# ESP32-WROVER_Dev_Board.net
KiCad netlist of a schematic drawn in Altium Designer
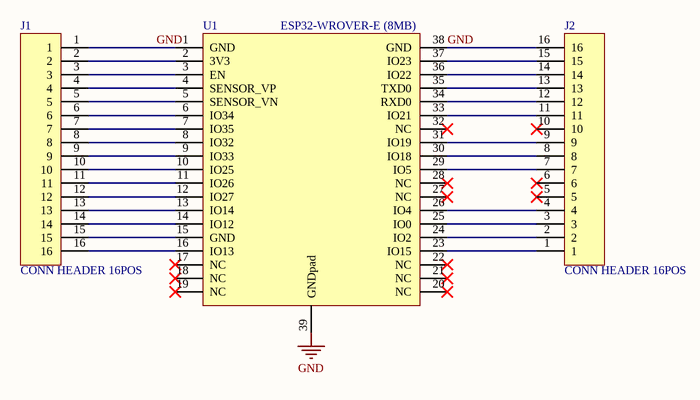
[diagram p0: ESP32-WROVER Dev Board.SchDoc]

(export (version "E")
  (design (tool "Eeschema 10.0.6"))
  (components
    (comp (ref "J1")
      (value "CONN HEADER 16POS")
      (footprint "CONN HEADER 16POS")
      (libsource (lib "") (part "CONN HEADER 16POS_1"))
    )
    (comp (ref "J2")
      (value "CONN HEADER 16POS")
      (footprint "CONN HEADER 16POS")
      (libsource (lib "G02_WSN") (part "CONN HEADER 16POS"))
    )
    (comp (ref "U1")
      (value "ESP32-WROVER-E (8MB)")
      (footprint "ESP32-WROVER-E (8MB)")
      (libsource (lib "G02_WSN") (part "ESP32-WROVER-E (8MB)"))
    )
  )
  (nets
    (net (code "1") (name "GND") (class "Default")
      (node (ref "J1") (pin "1") (pinfunction "1_1") (pintype "passive"))
      (node (ref "J2") (pin "16") (pinfunction "16_16") (pintype "passive"))
      (node (ref "U1") (pin "1") (pinfunction "GND_1") (pintype "passive"))
      (node (ref "U1") (pin "38") (pinfunction "GND_38") (pintype "passive"))
      (node (ref "U1") (pin "39") (pinfunction "GNDpad_39") (pintype "passive"))
    )
    (net (code "2") (name "Net-(J1-Pad15)") (class "Default")
      (node (ref "J1") (pin "15") (pinfunction "15_15") (pintype "passive"))
      (node (ref "U1") (pin "15") (pinfunction "GND_15") (pintype "passive"))
    )
    (net (code "3") (name "Net-(U1-3V3)") (class "Default")
      (node (ref "J1") (pin "2") (pinfunction "2_2") (pintype "passive"))
      (node (ref "U1") (pin "2") (pinfunction "3V3_2") (pintype "passive"))
    )
    (net (code "4") (name "Net-(U1-EN)") (class "Default")
      (node (ref "J1") (pin "3") (pinfunction "3_3") (pintype "passive"))
      (node (ref "U1") (pin "3") (pinfunction "EN_3") (pintype "passive"))
    )
    (net (code "5") (name "Net-(U1-IO0)") (class "Default")
      (node (ref "J2") (pin "3") (pinfunction "3_3") (pintype "passive"))
      (node (ref "U1") (pin "25") (pinfunction "IO0_25") (pintype "passive"))
    )
    (net (code "6") (name "Net-(U1-IO2)") (class "Default")
      (node (ref "J2") (pin "2") (pinfunction "2_2") (pintype "passive"))
      (node (ref "U1") (pin "24") (pinfunction "IO2_24") (pintype "passive"))
    )
    (net (code "7") (name "Net-(U1-IO4)") (class "Default")
      (node (ref "J2") (pin "4") (pinfunction "4_4") (pintype "passive"))
      (node (ref "U1") (pin "26") (pinfunction "IO4_26") (pintype "passive"))
    )
    (net (code "8") (name "Net-(U1-IO5)") (class "Default")
      (node (ref "J2") (pin "7") (pinfunction "7_7") (pintype "passive"))
      (node (ref "U1") (pin "29") (pinfunction "IO5_29") (pintype "passive"))
    )
    (net (code "9") (name "Net-(U1-IO12)") (class "Default")
      (node (ref "J1") (pin "14") (pinfunction "14_14") (pintype "passive"))
      (node (ref "U1") (pin "14") (pinfunction "IO12_14") (pintype "passive"))
    )
    (net (code "10") (name "Net-(U1-IO13)") (class "Default")
      (node (ref "J1") (pin "16") (pinfunction "16_16") (pintype "passive"))
      (node (ref "U1") (pin "16") (pinfunction "IO13_16") (pintype "passive"))
    )
    (net (code "11") (name "Net-(U1-IO14)") (class "Default")
      (node (ref "J1") (pin "13") (pinfunction "13_13") (pintype "passive"))
      (node (ref "U1") (pin "13") (pinfunction "IO14_13") (pintype "passive"))
    )
    (net (code "12") (name "Net-(U1-IO15)") (class "Default")
      (node (ref "J2") (pin "1") (pinfunction "1_1") (pintype "passive"))
      (node (ref "U1") (pin "23") (pinfunction "IO15_23") (pintype "passive"))
    )
    (net (code "13") (name "Net-(U1-IO18)") (class "Default")
      (node (ref "J2") (pin "8") (pinfunction "8_8") (pintype "passive"))
      (node (ref "U1") (pin "30") (pinfunction "IO18_30") (pintype "passive"))
    )
    (net (code "14") (name "Net-(U1-IO19)") (class "Default")
      (node (ref "J2") (pin "9") (pinfunction "9_9") (pintype "passive"))
      (node (ref "U1") (pin "31") (pinfunction "IO19_31") (pintype "passive"))
    )
    (net (code "15") (name "Net-(U1-IO21)") (class "Default")
      (node (ref "J2") (pin "11") (pinfunction "11_11") (pintype "passive"))
      (node (ref "U1") (pin "33") (pinfunction "IO21_33") (pintype "passive"))
    )
    (net (code "16") (name "Net-(U1-IO22)") (class "Default")
      (node (ref "J2") (pin "14") (pinfunction "14_14") (pintype "passive"))
      (node (ref "U1") (pin "36") (pinfunction "IO22_36") (pintype "passive"))
    )
    (net (code "17") (name "Net-(U1-IO23)") (class "Default")
      (node (ref "J2") (pin "15") (pinfunction "15_15") (pintype "passive"))
      (node (ref "U1") (pin "37") (pinfunction "IO23_37") (pintype "passive"))
    )
    (net (code "18") (name "Net-(U1-IO25)") (class "Default")
      (node (ref "J1") (pin "10") (pinfunction "10_10") (pintype "passive"))
      (node (ref "U1") (pin "10") (pinfunction "IO25_10") (pintype "passive"))
    )
    (net (code "19") (name "Net-(U1-IO26)") (class "Default")
      (node (ref "J1") (pin "11") (pinfunction "11_11") (pintype "passive"))
      (node (ref "U1") (pin "11") (pinfunction "IO26_11") (pintype "passive"))
    )
    (net (code "20") (name "Net-(U1-IO27)") (class "Default")
      (node (ref "J1") (pin "12") (pinfunction "12_12") (pintype "passive"))
      (node (ref "U1") (pin "12") (pinfunction "IO27_12") (pintype "passive"))
    )
    (net (code "21") (name "Net-(U1-IO32)") (class "Default")
      (node (ref "J1") (pin "8") (pinfunction "8_8") (pintype "passive"))
      (node (ref "U1") (pin "8") (pinfunction "IO32_8") (pintype "passive"))
    )
    (net (code "22") (name "Net-(U1-IO33)") (class "Default")
      (node (ref "J1") (pin "9") (pinfunction "9_9") (pintype "passive"))
      (node (ref "U1") (pin "9") (pinfunction "IO33_9") (pintype "passive"))
    )
    (net (code "23") (name "Net-(U1-IO34)") (class "Default")
      (node (ref "J1") (pin "6") (pinfunction "6_6") (pintype "passive"))
      (node (ref "U1") (pin "6") (pinfunction "IO34_6") (pintype "passive"))
    )
    (net (code "24") (name "Net-(U1-IO35)") (class "Default")
      (node (ref "J1") (pin "7") (pinfunction "7_7") (pintype "passive"))
      (node (ref "U1") (pin "7") (pinfunction "IO35_7") (pintype "passive"))
    )
    (net (code "25") (name "Net-(U1-RXD0)") (class "Default")
      (node (ref "J2") (pin "12") (pinfunction "12_12") (pintype "passive"))
      (node (ref "U1") (pin "34") (pinfunction "RXD0_34") (pintype "passive"))
    )
    (net (code "26") (name "Net-(U1-SENSOR_VN)") (class "Default")
      (node (ref "J1") (pin "5") (pinfunction "5_5") (pintype "passive"))
      (node (ref "U1") (pin "5") (pinfunction "SENSOR_VN_5") (pintype "passive"))
    )
    (net (code "27") (name "Net-(U1-SENSOR_VP)") (class "Default")
      (node (ref "J1") (pin "4") (pinfunction "4_4") (pintype "passive"))
      (node (ref "U1") (pin "4") (pinfunction "SENSOR_VP_4") (pintype "passive"))
    )
    (net (code "28") (name "Net-(U1-TXD0)") (class "Default")
      (node (ref "J2") (pin "13") (pinfunction "13_13") (pintype "passive"))
      (node (ref "U1") (pin "35") (pinfunction "TXD0_35") (pintype "passive"))
    )
    (net (code "29") (name "unconnected-(J2-Pad5)") (class "Default")
      (node (ref "J2") (pin "5") (pinfunction "5_5") (pintype "passive+no_connect"))
    )
    (net (code "30") (name "unconnected-(J2-Pad6)") (class "Default")
      (node (ref "J2") (pin "6") (pinfunction "6_6") (pintype "passive+no_connect"))
    )
    (net (code "31") (name "unconnected-(J2-Pad10)") (class "Default")
      (node (ref "J2") (pin "10") (pinfunction "10_10") (pintype "passive+no_connect"))
    )
    (net (code "32") (name "unconnected-(U1-NC-Pad17)") (class "Default")
      (node (ref "U1") (pin "17") (pinfunction "NC_17") (pintype "passive+no_connect"))
    )
    (net (code "33") (name "unconnected-(U1-NC-Pad18)") (class "Default")
      (node (ref "U1") (pin "18") (pinfunction "NC_18") (pintype "passive+no_connect"))
    )
    (net (code "34") (name "unconnected-(U1-NC-Pad19)") (class "Default")
      (node (ref "U1") (pin "19") (pinfunction "NC_19") (pintype "passive+no_connect"))
    )
    (net (code "35") (name "unconnected-(U1-NC-Pad20)") (class "Default")
      (node (ref "U1") (pin "20") (pinfunction "NC_20") (pintype "passive+no_connect"))
    )
    (net (code "36") (name "unconnected-(U1-NC-Pad21)") (class "Default")
      (node (ref "U1") (pin "21") (pinfunction "NC_21") (pintype "passive+no_connect"))
    )
    (net (code "37") (name "unconnected-(U1-NC-Pad22)") (class "Default")
      (node (ref "U1") (pin "22") (pinfunction "NC_22") (pintype "passive+no_connect"))
    )
    (net (code "38") (name "unconnected-(U1-NC-Pad27)") (class "Default")
      (node (ref "U1") (pin "27") (pinfunction "NC_27") (pintype "passive+no_connect"))
    )
    (net (code "39") (name "unconnected-(U1-NC-Pad28)") (class "Default")
      (node (ref "U1") (pin "28") (pinfunction "NC_28") (pintype "passive+no_connect"))
    )
    (net (code "40") (name "unconnected-(U1-NC-Pad32)") (class "Default")
      (node (ref "U1") (pin "32") (pinfunction "NC_32") (pintype "passive+no_connect"))
    )
  )
)
